# i2c_stm32.net
KiCad netlist of a schematic drawn in EAGLE
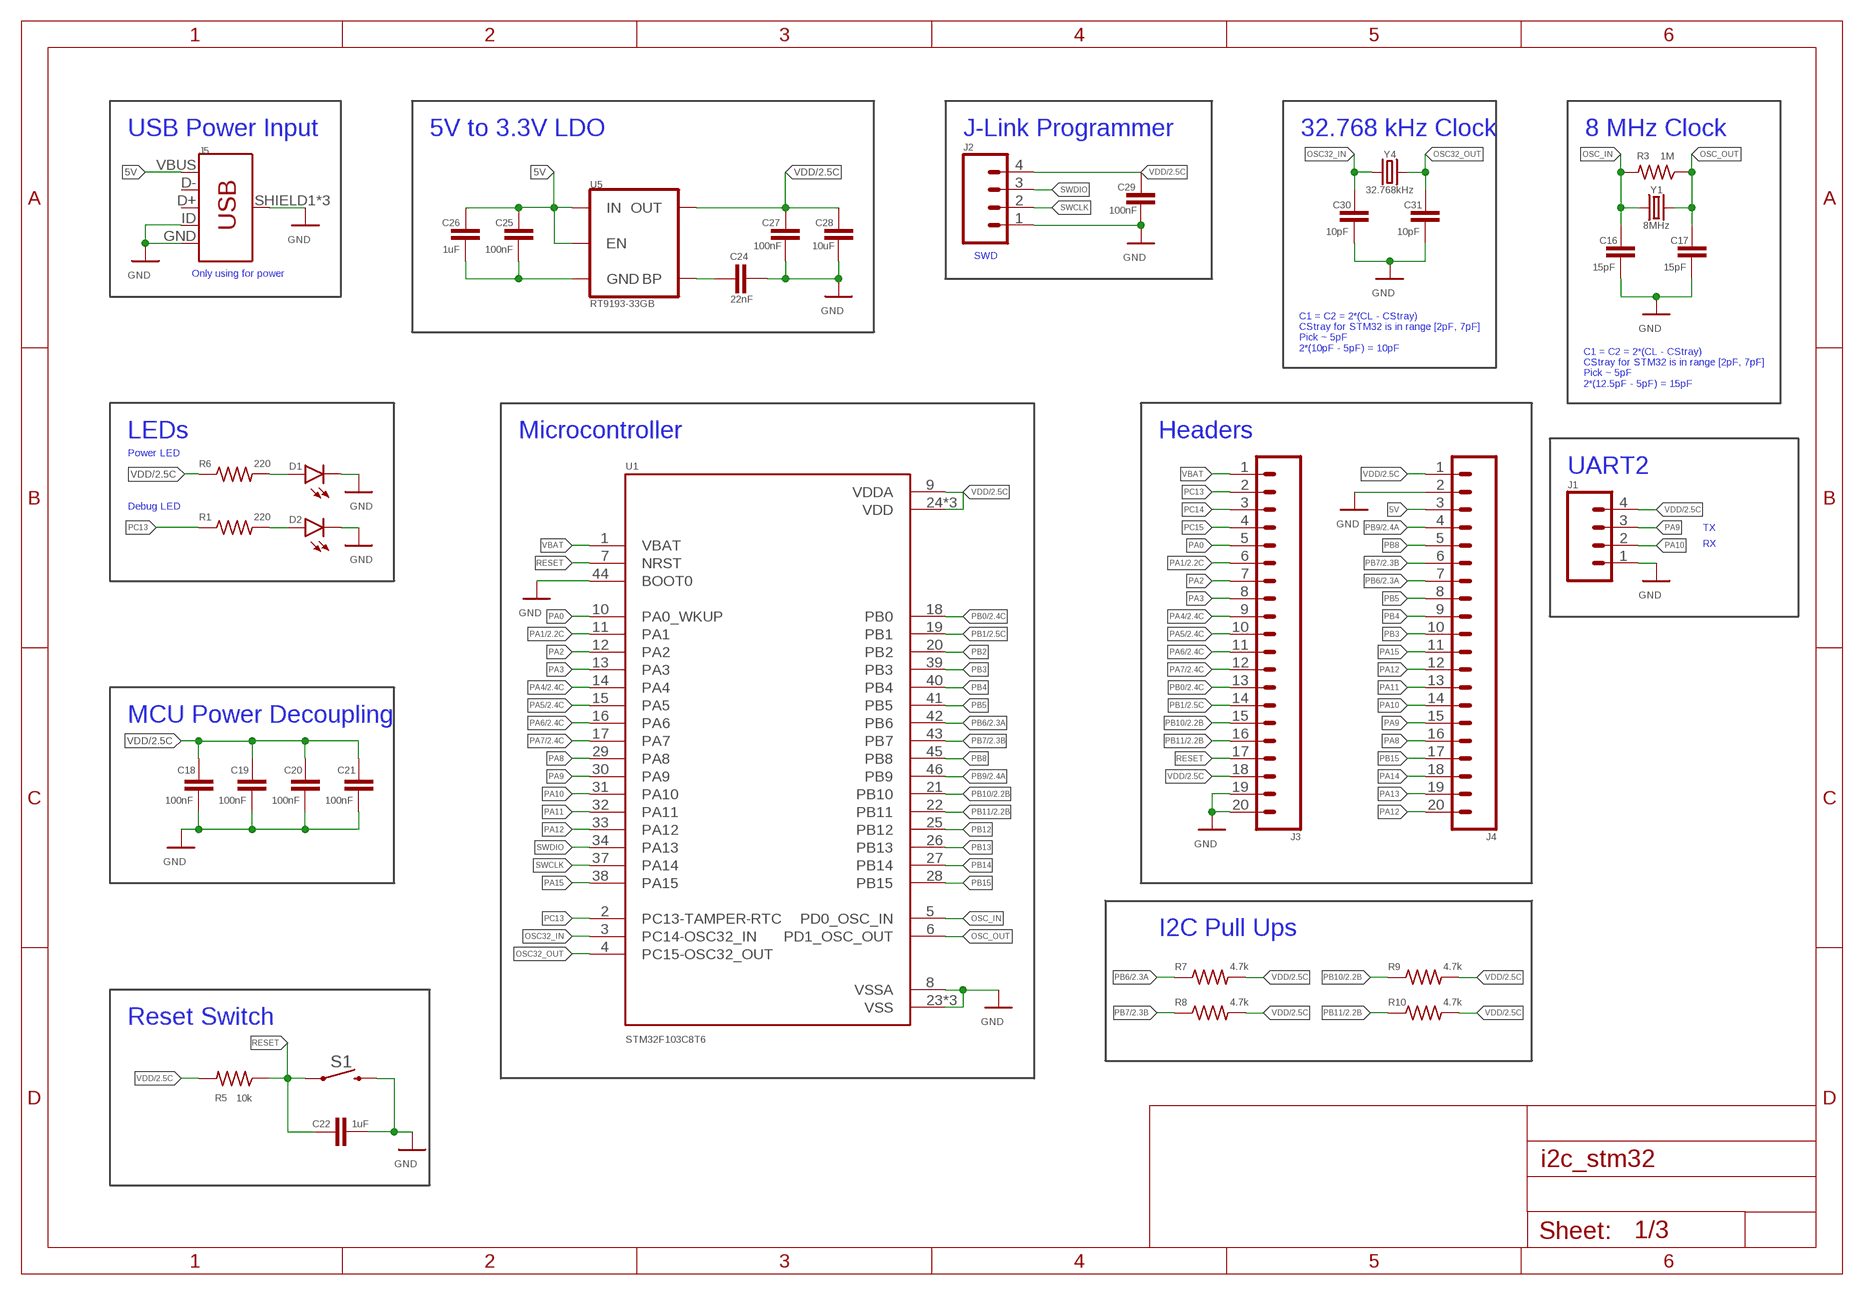
[diagram p0: schematic, sheet 1]
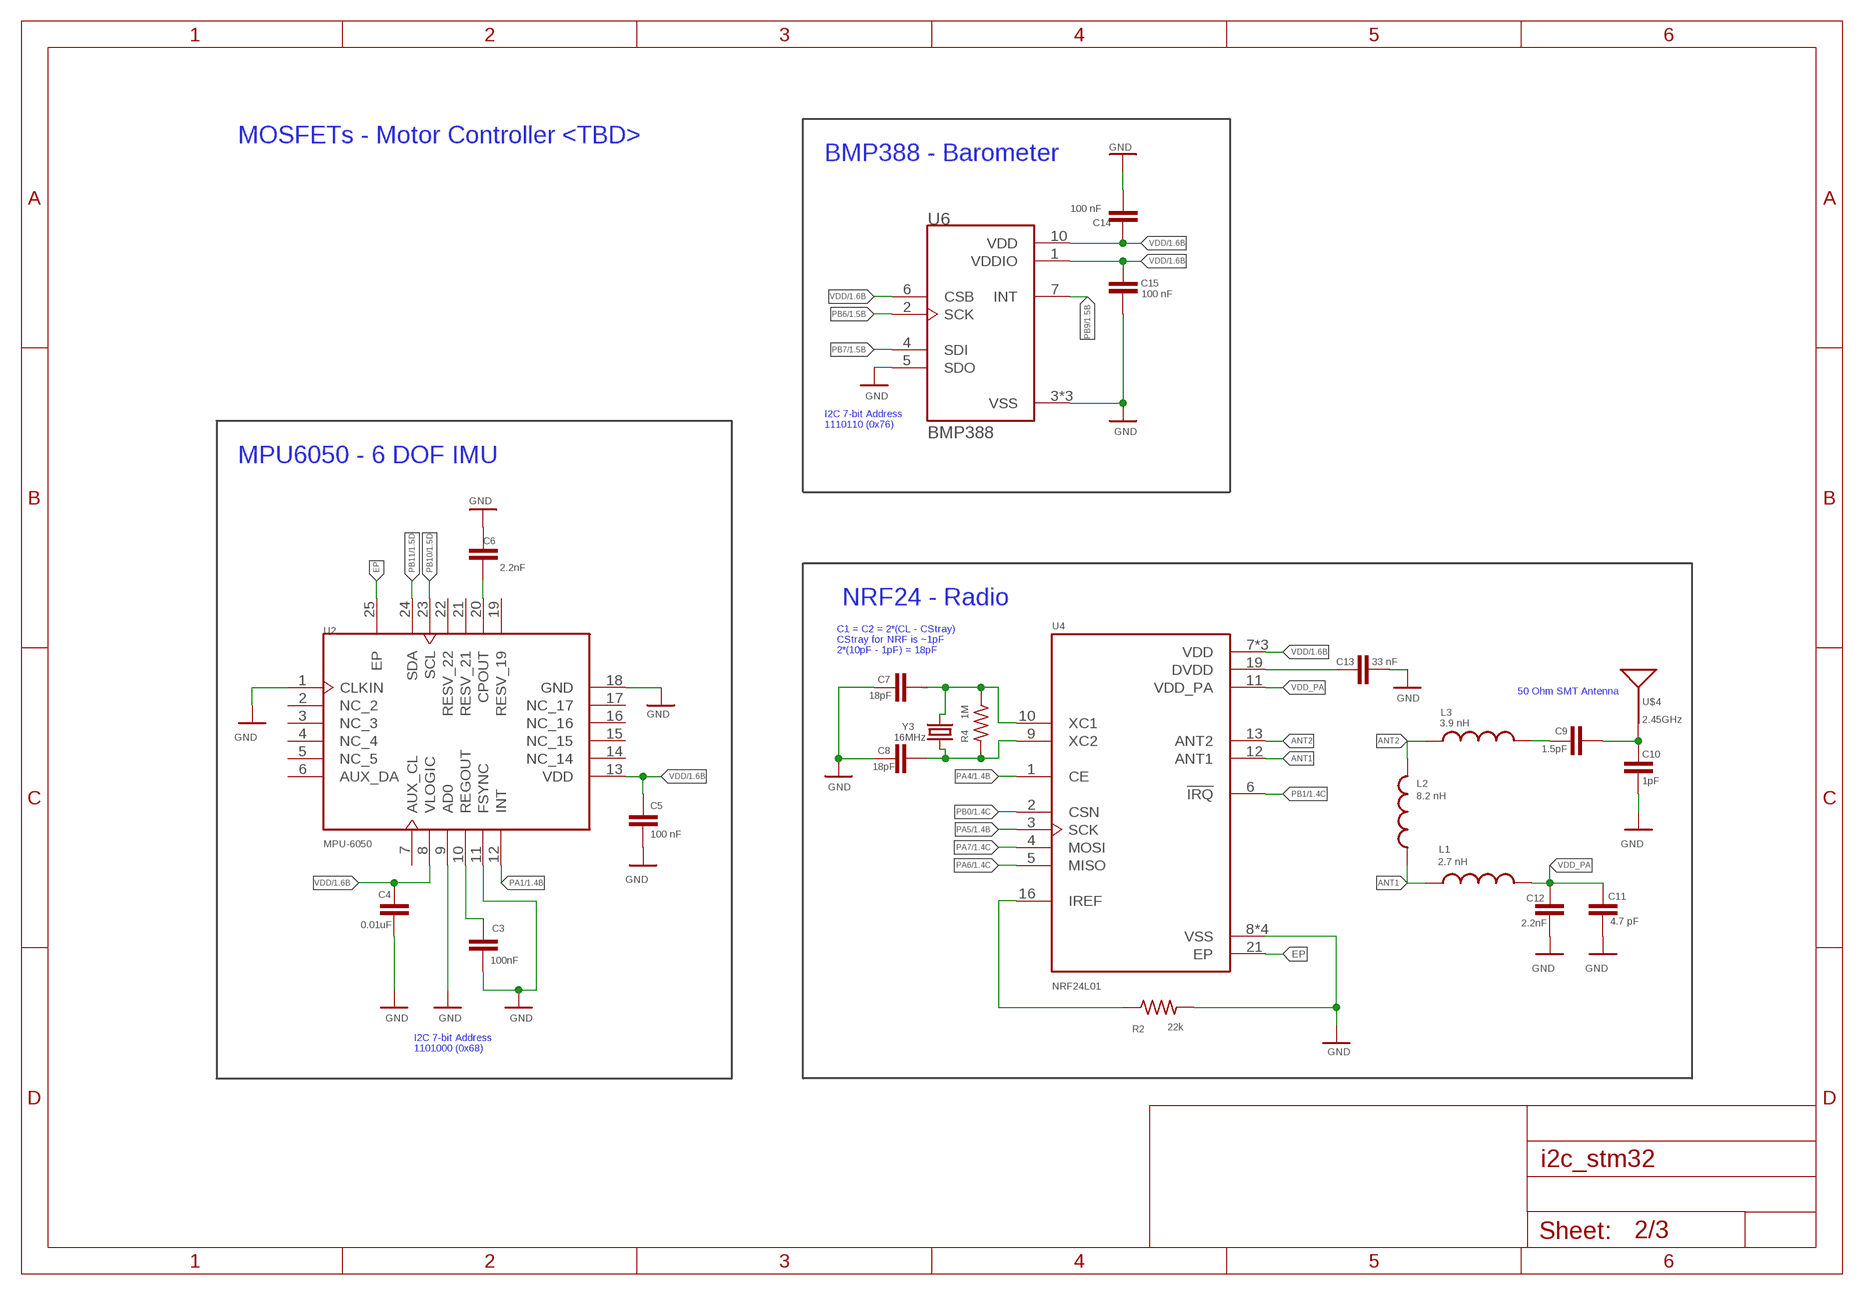
[diagram p1: schematic, sheet 2]
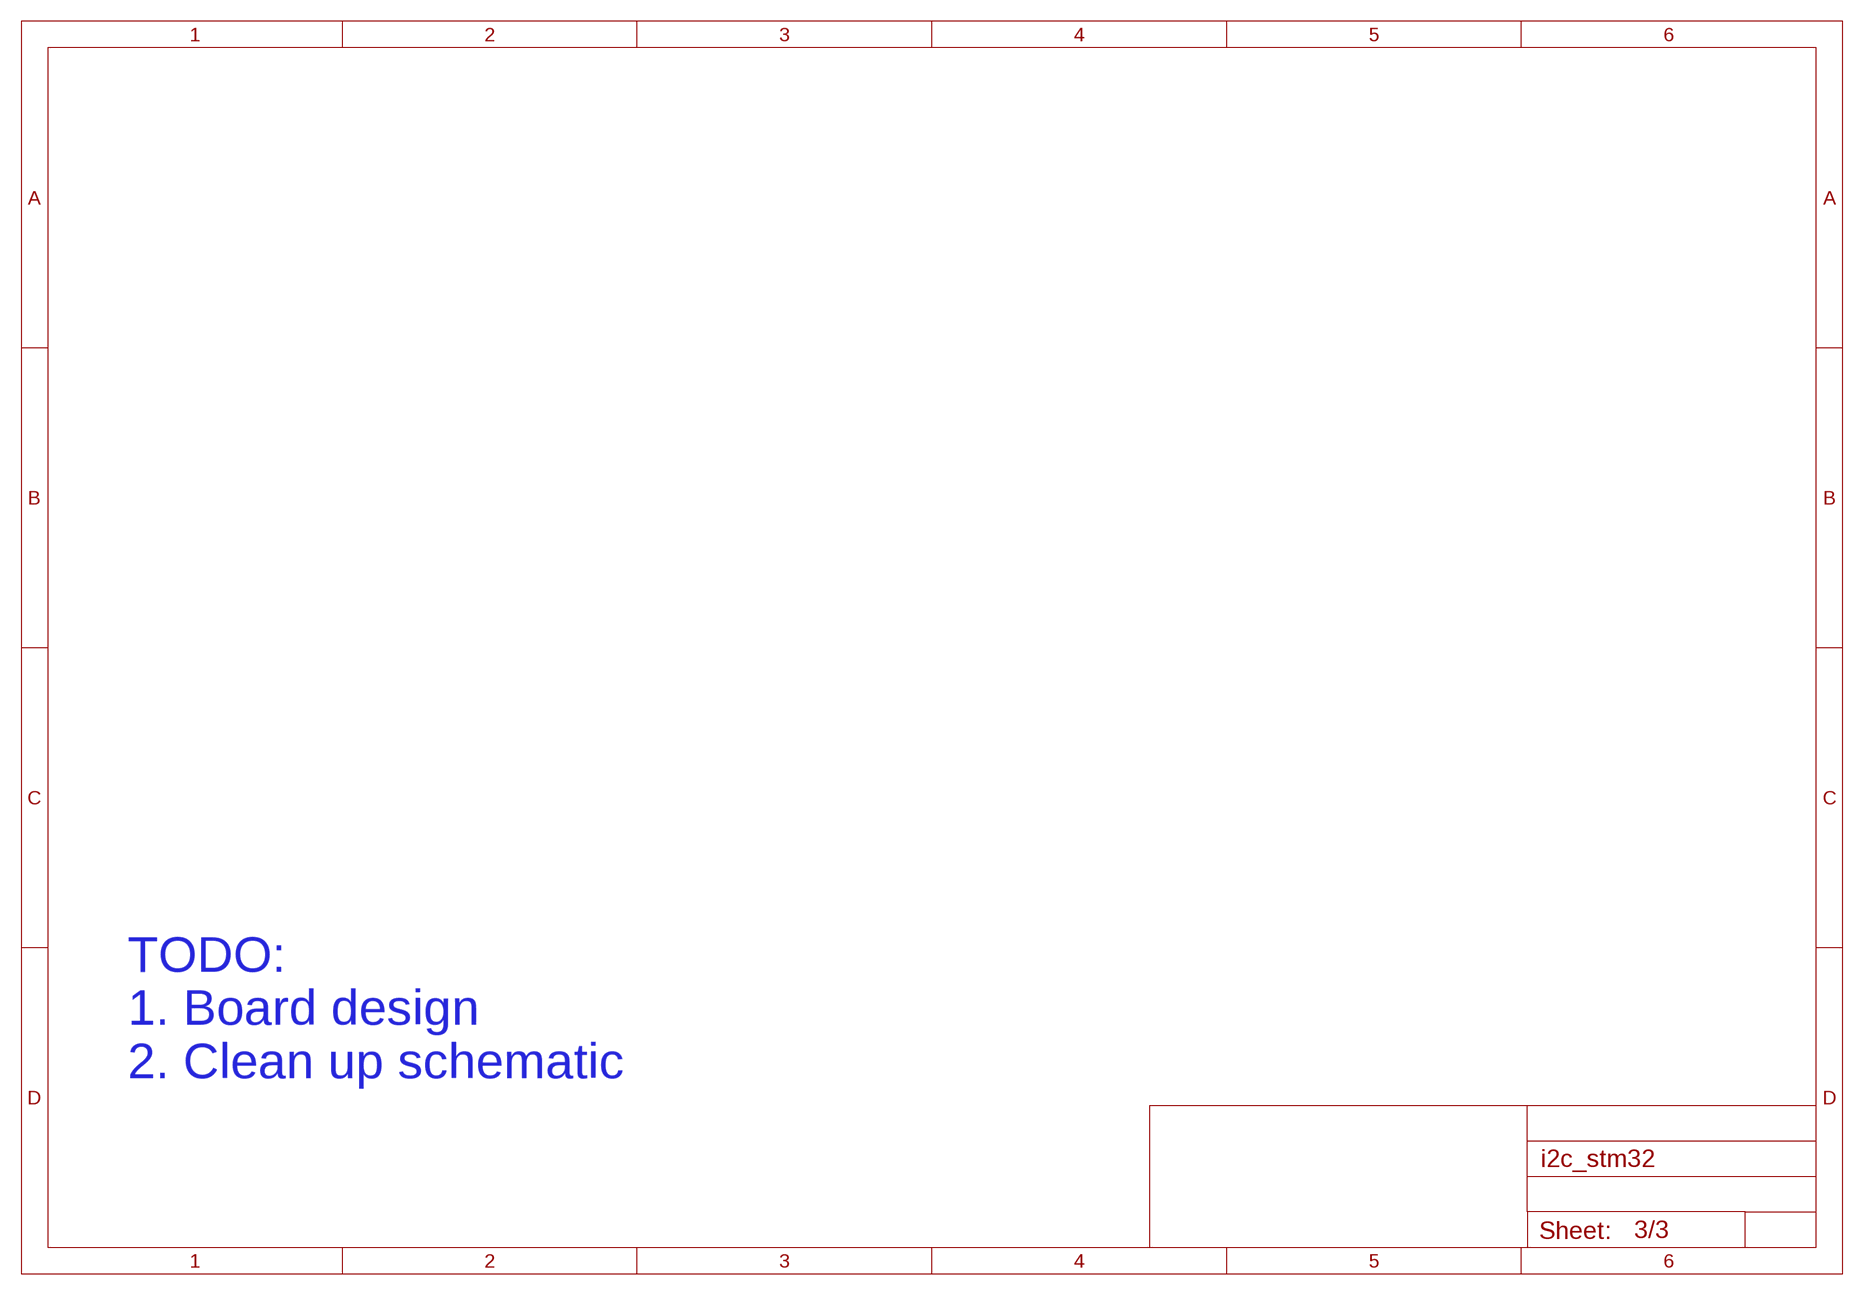
[diagram p2: schematic, sheet 3]

(export (version "E")
  (design (tool "Eeschema 10.0.6"))
  (components
    (comp (ref "C3")
      (value "100nF")
      (footprint "eagle-import:CAP_0603")
      (fields
        (field (name "DIGIKEY_PART_NUMBER") "399-7814-2-ND")
        (field (name "MANUFACTURER") "KEMET")
        (field (name "MPN") "C0603C100C5GACTU")
        (field (name "CREATED_BY") "PCBLayout.com")
      )
      (libsource (lib "eagle-import") (part "C0603C100C5GACTU"))
    )
    (comp (ref "C4")
      (value "0.01uF")
      (footprint "eagle-import:CAP_0603")
      (fields
        (field (name "DIGIKEY_PART_NUMBER") "399-7814-2-ND")
        (field (name "MANUFACTURER") "KEMET")
        (field (name "MPN") "C0603C100C5GACTU")
        (field (name "CREATED_BY") "PCBLayout.com")
      )
      (libsource (lib "eagle-import") (part "C0603C100C5GACTU"))
    )
    (comp (ref "C5")
      (value "100 nF")
      (footprint "eagle-import:CAP_0603")
      (fields
        (field (name "DIGIKEY_PART_NUMBER") "399-7814-2-ND")
        (field (name "MANUFACTURER") "KEMET")
        (field (name "MPN") "C0603C100C5GACTU")
        (field (name "CREATED_BY") "PCBLayout.com")
      )
      (libsource (lib "eagle-import") (part "C0603C100C5GACTU"))
    )
    (comp (ref "C6")
      (value "2.2nF")
      (footprint "eagle-import:CAP_0603")
      (fields
        (field (name "DIGIKEY_PART_NUMBER") "399-7814-2-ND")
        (field (name "MANUFACTURER") "KEMET")
        (field (name "MPN") "C0603C100C5GACTU")
        (field (name "CREATED_BY") "PCBLayout.com")
      )
      (libsource (lib "eagle-import") (part "C0603C100C5GACTU"))
    )
    (comp (ref "C7")
      (value "18pF")
      (footprint "eagle-import:CAP_0603")
      (fields
        (field (name "DIGIKEY_PART_NUMBER") "399-7814-2-ND")
        (field (name "MANUFACTURER") "KEMET")
        (field (name "MPN") "C0603C100C5GACTU")
        (field (name "CREATED_BY") "PCBLayout.com")
      )
      (libsource (lib "eagle-import") (part "C0603C100C5GACTU"))
    )
    (comp (ref "C8")
      (value "18pF")
      (footprint "eagle-import:CAP_0603")
      (fields
        (field (name "DIGIKEY_PART_NUMBER") "399-7814-2-ND")
        (field (name "MANUFACTURER") "KEMET")
        (field (name "MPN") "C0603C100C5GACTU")
        (field (name "CREATED_BY") "PCBLayout.com")
      )
      (libsource (lib "eagle-import") (part "C0603C100C5GACTU"))
    )
    (comp (ref "C9")
      (value "1.5pF")
      (footprint "eagle-import:CAP_0603")
      (fields
        (field (name "DIGIKEY_PART_NUMBER") "399-7814-2-ND")
        (field (name "MANUFACTURER") "KEMET")
        (field (name "MPN") "C0603C100C5GACTU")
        (field (name "CREATED_BY") "PCBLayout.com")
      )
      (libsource (lib "eagle-import") (part "C0603C100C5GACTU"))
    )
    (comp (ref "C10")
      (value "1pF")
      (footprint "eagle-import:CAP_0603")
      (fields
        (field (name "DIGIKEY_PART_NUMBER") "399-7814-2-ND")
        (field (name "MANUFACTURER") "KEMET")
        (field (name "MPN") "C0603C100C5GACTU")
        (field (name "CREATED_BY") "PCBLayout.com")
      )
      (libsource (lib "eagle-import") (part "C0603C100C5GACTU"))
    )
    (comp (ref "C11")
      (value "4.7 pF")
      (footprint "eagle-import:CAP_0603")
      (fields
        (field (name "DIGIKEY_PART_NUMBER") "399-7814-2-ND")
        (field (name "MANUFACTURER") "KEMET")
        (field (name "MPN") "C0603C100C5GACTU")
        (field (name "CREATED_BY") "PCBLayout.com")
      )
      (libsource (lib "eagle-import") (part "C0603C100C5GACTU"))
    )
    (comp (ref "C12")
      (value "2.2nF")
      (footprint "eagle-import:CAP_0603")
      (fields
        (field (name "DIGIKEY_PART_NUMBER") "399-7814-2-ND")
        (field (name "MANUFACTURER") "KEMET")
        (field (name "MPN") "C0603C100C5GACTU")
        (field (name "CREATED_BY") "PCBLayout.com")
      )
      (libsource (lib "eagle-import") (part "C0603C100C5GACTU"))
    )
    (comp (ref "C13")
      (value "33 nF")
      (footprint "eagle-import:CAP_0603")
      (fields
        (field (name "DIGIKEY_PART_NUMBER") "399-7814-2-ND")
        (field (name "MANUFACTURER") "KEMET")
        (field (name "MPN") "C0603C100C5GACTU")
        (field (name "CREATED_BY") "PCBLayout.com")
      )
      (libsource (lib "eagle-import") (part "C0603C100C5GACTU"))
    )
    (comp (ref "C14")
      (value "100 nF")
      (footprint "eagle-import:CAP_0603")
      (fields
        (field (name "DIGIKEY_PART_NUMBER") "399-7814-2-ND")
        (field (name "MANUFACTURER") "KEMET")
        (field (name "MPN") "C0603C100C5GACTU")
        (field (name "CREATED_BY") "PCBLayout.com")
      )
      (libsource (lib "eagle-import") (part "C0603C100C5GACTU"))
    )
    (comp (ref "C15")
      (value "100 nF")
      (footprint "eagle-import:CAP_0603")
      (fields
        (field (name "DIGIKEY_PART_NUMBER") "399-7814-2-ND")
        (field (name "MANUFACTURER") "KEMET")
        (field (name "MPN") "C0603C100C5GACTU")
        (field (name "CREATED_BY") "PCBLayout.com")
      )
      (libsource (lib "eagle-import") (part "C0603C100C5GACTU"))
    )
    (comp (ref "L1")
      (value "2.7 nH")
      (footprint "eagle-import:RESC0603_M")
      (libsource (lib "eagle-import") (part "INDUCTOR_0603_M"))
    )
    (comp (ref "L2")
      (value "8.2 nH")
      (footprint "eagle-import:RESC0603_M")
      (libsource (lib "eagle-import") (part "INDUCTOR_0603_M"))
    )
    (comp (ref "L3")
      (value "3.9 nH")
      (footprint "eagle-import:RESC0603_M")
      (libsource (lib "eagle-import") (part "INDUCTOR_0603_M"))
    )
    (comp (ref "R2")
      (value "22k")
      (footprint "eagle-import:RES_0603")
      (fields
        (field (name "DIGIKEY_PART_NUMBER") "311-0.0GRTR-ND")
        (field (name "MANUFACTURER") "Yageo")
        (field (name "MPN") "RC0603JR-070RL")
        (field (name "CREATED_BY") "PCBLayout.com")
      )
      (libsource (lib "eagle-import") (part "RC0603JR-070RL"))
    )
    (comp (ref "R4")
      (value "1M")
      (footprint "eagle-import:RES_0603")
      (fields
        (field (name "DIGIKEY_PART_NUMBER") "311-0.0GRTR-ND")
        (field (name "MANUFACTURER") "Yageo")
        (field (name "MPN") "RC0603JR-070RL")
        (field (name "CREATED_BY") "PCBLayout.com")
      )
      (libsource (lib "eagle-import") (part "RC0603JR-070RL"))
    )
    (comp (ref "U$4")
      (value "2.45GHz")
      (footprint "eagle-import:ANT-2.4GHZ-6.5X2.2MM")
      (libsource (lib "eagle-import") (part "ANTENNA2.4GHZ-6.5X2.2MM"))
    )
    (comp (ref "U2")
      (value "MPU-6050")
      (footprint "eagle-import:24-VFQFN")
      (fields
        (field (name "DIGIKEY_PART_NUMBER") "1428-1007-1-ND")
        (field (name "MANUFACTURER") "TDK InvenSense")
        (field (name "CREATED_BY") "PCBLayout.com")
      )
      (libsource (lib "eagle-import") (part "MPU-6050"))
    )
    (comp (ref "U4")
      (value "NRF24L01")
      (footprint "eagle-import:QFN50P400X400X95-21N")
      (fields (field (name "MF") "Nordic"))
      (libsource (lib "eagle-import") (part "NRF24L01"))
    )
    (comp (ref "U6")
      (value "BMP388")
      (footprint "eagle-import:PQFN50P200X200X80-10N")
      (fields (field (name "DIGI-KEY_PART_NUMBER") "828-1079-1-ND") (field (name "MF") "Bosch Sensortec"))
      (libsource (lib "eagle-import") (part "BMP388"))
    )
    (comp (ref "Y3")
      (value "16MHz")
      (footprint "eagle-import:CRYSTAL-SMD-5X3.2-4PAD")
      (libsource (lib "eagle-import") (part "CRYSTAL-16MHZSMD-5X3.2"))
    )
    (comp (ref "C16")
      (value "15pF")
      (footprint "eagle-import:CAP_0603")
      (fields
        (field (name "DIGIKEY_PART_NUMBER") "399-7814-2-ND")
        (field (name "MANUFACTURER") "KEMET")
        (field (name "MPN") "C0603C100C5GACTU")
        (field (name "CREATED_BY") "PCBLayout.com")
      )
      (libsource (lib "eagle-import") (part "C0603C100C5GACTU"))
    )
    (comp (ref "C17")
      (value "15pF")
      (footprint "eagle-import:CAP_0603")
      (fields
        (field (name "DIGIKEY_PART_NUMBER") "399-7814-2-ND")
        (field (name "MANUFACTURER") "KEMET")
        (field (name "MPN") "C0603C100C5GACTU")
        (field (name "CREATED_BY") "PCBLayout.com")
      )
      (libsource (lib "eagle-import") (part "C0603C100C5GACTU"))
    )
    (comp (ref "C18")
      (value "100nF")
      (footprint "eagle-import:CAP_0603")
      (fields
        (field (name "DIGIKEY_PART_NUMBER") "399-7814-2-ND")
        (field (name "MANUFACTURER") "KEMET")
        (field (name "MPN") "C0603C100C5GACTU")
        (field (name "CREATED_BY") "PCBLayout.com")
      )
      (libsource (lib "eagle-import") (part "C0603C100C5GACTU"))
    )
    (comp (ref "C19")
      (value "100nF")
      (footprint "eagle-import:CAP_0603")
      (fields
        (field (name "DIGIKEY_PART_NUMBER") "399-7814-2-ND")
        (field (name "MANUFACTURER") "KEMET")
        (field (name "MPN") "C0603C100C5GACTU")
        (field (name "CREATED_BY") "PCBLayout.com")
      )
      (libsource (lib "eagle-import") (part "C0603C100C5GACTU"))
    )
    (comp (ref "C20")
      (value "100nF")
      (footprint "eagle-import:CAP_0603")
      (fields
        (field (name "DIGIKEY_PART_NUMBER") "399-7814-2-ND")
        (field (name "MANUFACTURER") "KEMET")
        (field (name "MPN") "C0603C100C5GACTU")
        (field (name "CREATED_BY") "PCBLayout.com")
      )
      (libsource (lib "eagle-import") (part "C0603C100C5GACTU"))
    )
    (comp (ref "C21")
      (value "100nF")
      (footprint "eagle-import:CAP_0603")
      (fields
        (field (name "DIGIKEY_PART_NUMBER") "399-7814-2-ND")
        (field (name "MANUFACTURER") "KEMET")
        (field (name "MPN") "C0603C100C5GACTU")
        (field (name "CREATED_BY") "PCBLayout.com")
      )
      (libsource (lib "eagle-import") (part "C0603C100C5GACTU"))
    )
    (comp (ref "C22")
      (value "1uF")
      (footprint "eagle-import:CAP_0603")
      (fields
        (field (name "DIGIKEY_PART_NUMBER") "399-7814-2-ND")
        (field (name "MANUFACTURER") "KEMET")
        (field (name "MPN") "C0603C100C5GACTU")
        (field (name "CREATED_BY") "PCBLayout.com")
      )
      (libsource (lib "eagle-import") (part "C0603C100C5GACTU"))
    )
    (comp (ref "C24")
      (value "22nF")
      (footprint "eagle-import:CAP_0603")
      (fields
        (field (name "DIGIKEY_PART_NUMBER") "399-7814-2-ND")
        (field (name "MANUFACTURER") "KEMET")
        (field (name "MPN") "C0603C100C5GACTU")
        (field (name "CREATED_BY") "PCBLayout.com")
      )
      (libsource (lib "eagle-import") (part "C0603C100C5GACTU"))
    )
    (comp (ref "C25")
      (value "100nF")
      (footprint "eagle-import:CAP_0603")
      (fields
        (field (name "DIGIKEY_PART_NUMBER") "399-7814-2-ND")
        (field (name "MANUFACTURER") "KEMET")
        (field (name "MPN") "C0603C100C5GACTU")
        (field (name "CREATED_BY") "PCBLayout.com")
      )
      (libsource (lib "eagle-import") (part "C0603C100C5GACTU"))
    )
    (comp (ref "C26")
      (value "1uF")
      (footprint "eagle-import:CAP_0603")
      (fields
        (field (name "DIGIKEY_PART_NUMBER") "399-7814-2-ND")
        (field (name "MANUFACTURER") "KEMET")
        (field (name "MPN") "C0603C100C5GACTU")
        (field (name "CREATED_BY") "PCBLayout.com")
      )
      (libsource (lib "eagle-import") (part "C0603C100C5GACTU"))
    )
    (comp (ref "C27")
      (value "100nF")
      (footprint "eagle-import:CAP_0603")
      (fields
        (field (name "DIGIKEY_PART_NUMBER") "399-7814-2-ND")
        (field (name "MANUFACTURER") "KEMET")
        (field (name "MPN") "C0603C100C5GACTU")
        (field (name "CREATED_BY") "PCBLayout.com")
      )
      (libsource (lib "eagle-import") (part "C0603C100C5GACTU"))
    )
    (comp (ref "C28")
      (value "10uF")
      (footprint "eagle-import:CAP_0603")
      (fields
        (field (name "DIGIKEY_PART_NUMBER") "399-7814-2-ND")
        (field (name "MANUFACTURER") "KEMET")
        (field (name "MPN") "C0603C100C5GACTU")
        (field (name "CREATED_BY") "PCBLayout.com")
      )
      (libsource (lib "eagle-import") (part "C0603C100C5GACTU"))
    )
    (comp (ref "C29")
      (value "100nF")
      (footprint "eagle-import:CAP_0603")
      (fields
        (field (name "DIGIKEY_PART_NUMBER") "399-7814-2-ND")
        (field (name "MANUFACTURER") "KEMET")
        (field (name "MPN") "C0603C100C5GACTU")
        (field (name "CREATED_BY") "PCBLayout.com")
      )
      (libsource (lib "eagle-import") (part "C0603C100C5GACTU"))
    )
    (comp (ref "C30")
      (value "10pF")
      (footprint "eagle-import:CAP_0603")
      (fields
        (field (name "DIGIKEY_PART_NUMBER") "399-7814-2-ND")
        (field (name "MANUFACTURER") "KEMET")
        (field (name "MPN") "C0603C100C5GACTU")
        (field (name "CREATED_BY") "PCBLayout.com")
      )
      (libsource (lib "eagle-import") (part "C0603C100C5GACTU"))
    )
    (comp (ref "C31")
      (value "10pF")
      (footprint "eagle-import:CAP_0603")
      (fields
        (field (name "DIGIKEY_PART_NUMBER") "399-7814-2-ND")
        (field (name "MANUFACTURER") "KEMET")
        (field (name "MPN") "C0603C100C5GACTU")
        (field (name "CREATED_BY") "PCBLayout.com")
      )
      (libsource (lib "eagle-import") (part "C0603C100C5GACTU"))
    )
    (comp (ref "D1")
      (value "LED0603")
      (footprint "eagle-import:LED-0603")
      (libsource (lib "eagle-import") (part "LED0603"))
    )
    (comp (ref "D2")
      (value "LED0603")
      (footprint "eagle-import:LED-0603")
      (libsource (lib "eagle-import") (part "LED0603"))
    )
    (comp (ref "J1")
      (value "CONN_04")
      (footprint "eagle-import:1X04")
      (libsource (lib "eagle-import") (part "CONN_04"))
    )
    (comp (ref "J2")
      (value "CONN_04")
      (footprint "eagle-import:1X04")
      (libsource (lib "eagle-import") (part "CONN_04"))
    )
    (comp (ref "J3")
      (value "CONN_20")
      (footprint "eagle-import:1X20")
      (libsource (lib "eagle-import") (part "CONN_20"))
    )
    (comp (ref "J4")
      (value "CONN_20")
      (footprint "eagle-import:1X20")
      (libsource (lib "eagle-import") (part "CONN_20"))
    )
    (comp (ref "J5")
      (value "USB_MICRO-B_FEMALE-SMT")
      (footprint "eagle-import:USB-B-MICRO-SMD")
      (libsource (lib "eagle-import") (part "USB_MICRO-B_FEMALE-SMT"))
    )
    (comp (ref "R1")
      (value "220")
      (footprint "eagle-import:RES_0603")
      (fields
        (field (name "DIGIKEY_PART_NUMBER") "311-0.0GRTR-ND")
        (field (name "MANUFACTURER") "Yageo")
        (field (name "MPN") "RC0603JR-070RL")
        (field (name "CREATED_BY") "PCBLayout.com")
      )
      (libsource (lib "eagle-import") (part "RC0603JR-070RL"))
    )
    (comp (ref "R3")
      (value "1M")
      (footprint "eagle-import:RES_0603")
      (fields
        (field (name "DIGIKEY_PART_NUMBER") "311-0.0GRTR-ND")
        (field (name "MANUFACTURER") "Yageo")
        (field (name "MPN") "RC0603JR-070RL")
        (field (name "CREATED_BY") "PCBLayout.com")
      )
      (libsource (lib "eagle-import") (part "RC0603JR-070RL"))
    )
    (comp (ref "R5")
      (value "10k")
      (footprint "eagle-import:RES_0603")
      (fields
        (field (name "DIGIKEY_PART_NUMBER") "311-0.0GRTR-ND")
        (field (name "MANUFACTURER") "Yageo")
        (field (name "MPN") "RC0603JR-070RL")
        (field (name "CREATED_BY") "PCBLayout.com")
      )
      (libsource (lib "eagle-import") (part "RC0603JR-070RL"))
    )
    (comp (ref "R6")
      (value "220")
      (footprint "eagle-import:RES_0603")
      (fields
        (field (name "DIGIKEY_PART_NUMBER") "311-0.0GRTR-ND")
        (field (name "MANUFACTURER") "Yageo")
        (field (name "MPN") "RC0603JR-070RL")
        (field (name "CREATED_BY") "PCBLayout.com")
      )
      (libsource (lib "eagle-import") (part "RC0603JR-070RL"))
    )
    (comp (ref "R7")
      (value "4.7k")
      (footprint "eagle-import:RES_0603")
      (fields
        (field (name "DIGIKEY_PART_NUMBER") "311-0.0GRTR-ND")
        (field (name "MANUFACTURER") "Yageo")
        (field (name "MPN") "RC0603JR-070RL")
        (field (name "CREATED_BY") "PCBLayout.com")
      )
      (libsource (lib "eagle-import") (part "RC0603JR-070RL"))
    )
    (comp (ref "R8")
      (value "4.7k")
      (footprint "eagle-import:RES_0603")
      (fields
        (field (name "DIGIKEY_PART_NUMBER") "311-0.0GRTR-ND")
        (field (name "MANUFACTURER") "Yageo")
        (field (name "MPN") "RC0603JR-070RL")
        (field (name "CREATED_BY") "PCBLayout.com")
      )
      (libsource (lib "eagle-import") (part "RC0603JR-070RL"))
    )
    (comp (ref "R9")
      (value "4.7k")
      (footprint "eagle-import:RES_0603")
      (fields
        (field (name "DIGIKEY_PART_NUMBER") "311-0.0GRTR-ND")
        (field (name "MANUFACTURER") "Yageo")
        (field (name "MPN") "RC0603JR-070RL")
        (field (name "CREATED_BY") "PCBLayout.com")
      )
      (libsource (lib "eagle-import") (part "RC0603JR-070RL"))
    )
    (comp (ref "R10")
      (value "4.7k")
      (footprint "eagle-import:RES_0603")
      (fields
        (field (name "DIGIKEY_PART_NUMBER") "311-0.0GRTR-ND")
        (field (name "MANUFACTURER") "Yageo")
        (field (name "MPN") "RC0603JR-070RL")
        (field (name "CREATED_BY") "PCBLayout.com")
      )
      (libsource (lib "eagle-import") (part "RC0603JR-070RL"))
    )
    (comp (ref "S1")
      (value "MOMENTARY-SWITCH-SPST-PTH-6.0MM")
      (footprint "eagle-import:TACTILE_SWITCH_PTH_6.0MM")
      (libsource (lib "eagle-import") (part "MOMENTARY-SWITCH-SPST-PTH-6.0MM"))
    )
    (comp (ref "U1")
      (value "STM32F103C8T6")
      (footprint "eagle-import:QFP50P900X900X160-48N")
      (fields (field (name "MF") "STMicroelectronics") (field (name "SPICEPREFIX") "X"))
      (libsource (lib "eagle-import") (part "STM32F103C8T6"))
    )
    (comp (ref "U5")
      (value "RT9193-33GB")
      (footprint "eagle-import:SOT23-5")
      (libsource (lib "eagle-import") (part "V_REG_MIC5205ADJ"))
    )
    (comp (ref "Y1")
      (value "8MHz")
      (footprint "eagle-import:CRYSTAL-SMD-5X3.2-4PAD")
      (libsource (lib "eagle-import") (part "CRYSTAL-8MHZSMD-5X3.2"))
    )
    (comp (ref "Y4")
      (value "32.768kHz")
      (footprint "eagle-import:CRYSTAL-SMD-3.2X1.5MM")
      (libsource (lib "eagle-import") (part "CRYSTAL-32.768KHZSMD-3.2X1.5"))
    )
  )
  (nets
    (net (code "1") (name "5V") (class "Default")
      (node (ref "C25") (pin "2") (pinfunction "2_2") (pintype "passive"))
      (node (ref "C26") (pin "2") (pinfunction "2_2") (pintype "passive"))
      (node (ref "J4") (pin "3") (pinfunction "3_3") (pintype "passive"))
      (node (ref "J5") (pin "VBUS") (pinfunction "VBUS_VBUS") (pintype "power_in"))
      (node (ref "U5") (pin "1") (pinfunction "IN_1") (pintype "input"))
      (node (ref "U5") (pin "3") (pinfunction "EN_3") (pintype "input"))
    )
    (net (code "2") (name "ANT1") (class "Default")
      (node (ref "L1") (pin "1") (pinfunction "1_1") (pintype "passive"))
      (node (ref "L2") (pin "1") (pinfunction "1_1") (pintype "passive"))
      (node (ref "U4") (pin "12") (pinfunction "ANT1_12") (pintype "bidirectional"))
    )
    (net (code "3") (name "ANT2") (class "Default")
      (node (ref "L2") (pin "2") (pinfunction "2_2") (pintype "passive"))
      (node (ref "L3") (pin "1") (pinfunction "1_1") (pintype "passive"))
      (node (ref "U4") (pin "13") (pinfunction "ANT2_13") (pintype "bidirectional"))
    )
    (net (code "4") (name "EP") (class "Default")
      (node (ref "U2") (pin "25") (pinfunction "EP_25") (pintype "power_in"))
      (node (ref "U4") (pin "21") (pinfunction "EP_21") (pintype "power_in"))
    )
    (net (code "5") (name "GND") (class "Default")
      (node (ref "C10") (pin "1") (pinfunction "1_1") (pintype "passive"))
      (node (ref "C11") (pin "1") (pinfunction "1_1") (pintype "passive"))
      (node (ref "C12") (pin "1") (pinfunction "1_1") (pintype "passive"))
      (node (ref "C13") (pin "2") (pinfunction "2_2") (pintype "passive"))
      (node (ref "C14") (pin "2") (pinfunction "2_2") (pintype "passive"))
      (node (ref "C15") (pin "1") (pinfunction "1_1") (pintype "passive"))
      (node (ref "C16") (pin "2") (pinfunction "2_2") (pintype "passive"))
      (node (ref "C17") (pin "2") (pinfunction "2_2") (pintype "passive"))
      (node (ref "C18") (pin "2") (pinfunction "2_2") (pintype "passive"))
      (node (ref "C19") (pin "2") (pinfunction "2_2") (pintype "passive"))
      (node (ref "C20") (pin "2") (pinfunction "2_2") (pintype "passive"))
      (node (ref "C21") (pin "2") (pinfunction "2_2") (pintype "passive"))
      (node (ref "C22") (pin "2") (pinfunction "2_2") (pintype "passive"))
      (node (ref "C24") (pin "1") (pinfunction "1_1") (pintype "passive"))
      (node (ref "C27") (pin "2") (pinfunction "2_2") (pintype "passive"))
      (node (ref "C28") (pin "2") (pinfunction "2_2") (pintype "passive"))
      (node (ref "C29") (pin "2") (pinfunction "2_2") (pintype "passive"))
      (node (ref "C3") (pin "2") (pinfunction "2_2") (pintype "passive"))
      (node (ref "C30") (pin "2") (pinfunction "2_2") (pintype "passive"))
      (node (ref "C31") (pin "2") (pinfunction "2_2") (pintype "passive"))
      (node (ref "C4") (pin "2") (pinfunction "2_2") (pintype "passive"))
      (node (ref "C5") (pin "2") (pinfunction "2_2") (pintype "passive"))
      (node (ref "C6") (pin "2") (pinfunction "2_2") (pintype "passive"))
      (node (ref "C7") (pin "2") (pinfunction "2_2") (pintype "passive"))
      (node (ref "C8") (pin "2") (pinfunction "2_2") (pintype "passive"))
      (node (ref "D1") (pin "C") (pinfunction "C_C") (pintype "passive"))
      (node (ref "D2") (pin "C") (pinfunction "C_C") (pintype "passive"))
      (node (ref "J1") (pin "1") (pinfunction "1_1") (pintype "passive"))
      (node (ref "J2") (pin "1") (pinfunction "1_1") (pintype "passive"))
      (node (ref "J3") (pin "19") (pinfunction "19_19") (pintype "passive"))
      (node (ref "J3") (pin "20") (pinfunction "20_20") (pintype "passive"))
      (node (ref "J4") (pin "2") (pinfunction "2_2") (pintype "passive"))
      (node (ref "J5") (pin "GND") (pinfunction "GND_GND") (pintype "power_in"))
      (node (ref "J5") (pin "ID") (pinfunction "ID_ID") (pintype "bidirectional"))
      (node (ref "J5") (pin "SHIELD1") (pinfunction "SHIELD_SHIELD1") (pintype "bidirectional"))
      (node (ref "J5") (pin "SHIELD2") (pinfunction "SHIELD_SHIELD2") (pintype "bidirectional"))
      (node (ref "J5") (pin "SHIELD3") (pinfunction "SHIELD_SHIELD3") (pintype "bidirectional"))
      (node (ref "R2") (pin "2") (pinfunction "2_2") (pintype "passive"))
      (node (ref "S1") (pin "3") (pinfunction "2_3") (pintype "passive"))
      (node (ref "U1") (pin "23") (pinfunction "VSS_23") (pintype "power_in"))
      (node (ref "U1") (pin "35") (pinfunction "VSS_35") (pintype "power_in"))
      (node (ref "U1") (pin "44") (pinfunction "BOOT0_44") (pintype "input"))
      (node (ref "U1") (pin "47") (pinfunction "VSS_47") (pintype "power_in"))
      (node (ref "U1") (pin "8") (pinfunction "VSSA_8") (pintype "power_in"))
      (node (ref "U2") (pin "1") (pinfunction "CLKIN_1") (pintype "input"))
      (node (ref "U2") (pin "11") (pinfunction "FSYNC_11") (pintype "input"))
      (node (ref "U2") (pin "18") (pinfunction "GND_18") (pintype "power_in"))
      (node (ref "U2") (pin "9") (pinfunction "AD0_9") (pintype "bidirectional"))
      (node (ref "U4") (pin "14") (pinfunction "VSS_14") (pintype "power_in"))
      (node (ref "U4") (pin "17") (pinfunction "VSS_17") (pintype "power_in"))
      (node (ref "U4") (pin "20") (pinfunction "VSS_20") (pintype "power_in"))
      (node (ref "U4") (pin "8") (pinfunction "VSS_8") (pintype "power_in"))
      (node (ref "U6") (pin "3") (pinfunction "VSS_3") (pintype "power_in"))
      (node (ref "U6") (pin "5") (pinfunction "SDO_5") (pintype "bidirectional"))
      (node (ref "U6") (pin "8") (pinfunction "VSS_8") (pintype "power_in"))
      (node (ref "U6") (pin "9") (pinfunction "VSS_9") (pintype "power_in"))
    )
    (net (code "6") (name "Net-(C9-Pad1)") (class "Default")
      (node (ref "C9") (pin "1") (pinfunction "1_1") (pintype "passive"))
      (node (ref "L3") (pin "2") (pinfunction "2_2") (pintype "passive"))
    )
    (net (code "7") (name "Net-(D1-PadA)") (class "Default")
      (node (ref "D1") (pin "A") (pinfunction "A_A") (pintype "passive"))
      (node (ref "R6") (pin "2") (pinfunction "2_2") (pintype "passive"))
    )
    (net (code "8") (name "Net-(D2-PadA)") (class "Default")
      (node (ref "D2") (pin "A") (pinfunction "A_A") (pintype "passive"))
      (node (ref "R1") (pin "2") (pinfunction "2_2") (pintype "passive"))
    )
    (net (code "9") (name "Net-(U$4-SIGNAL)") (class "Default")
      (node (ref "C10") (pin "2") (pinfunction "2_2") (pintype "passive"))
      (node (ref "C9") (pin "2") (pinfunction "2_2") (pintype "passive"))
      (node (ref "U$4") (pin "FEED") (pinfunction "SIGNAL_FEED") (pintype "bidirectional"))
    )
    (net (code "10") (name "Net-(U2-CPOUT)") (class "Default")
      (node (ref "C6") (pin "1") (pinfunction "1_1") (pintype "passive"))
      (node (ref "U2") (pin "20") (pinfunction "CPOUT_20") (pintype "output"))
    )
    (net (code "11") (name "Net-(U2-REGOUT)") (class "Default")
      (node (ref "C3") (pin "1") (pinfunction "1_1") (pintype "passive"))
      (node (ref "U2") (pin "10") (pinfunction "REGOUT_10") (pintype "passive"))
    )
    (net (code "12") (name "Net-(U4-DVDD)") (class "Default")
      (node (ref "C13") (pin "1") (pinfunction "1_1") (pintype "passive"))
      (node (ref "U4") (pin "19") (pinfunction "DVDD_19") (pintype "power_in"))
    )
    (net (code "13") (name "Net-(U4-IREF)") (class "Default")
      (node (ref "R2") (pin "1") (pinfunction "1_1") (pintype "passive"))
      (node (ref "U4") (pin "16") (pinfunction "IREF_16") (pintype "input"))
    )
    (net (code "14") (name "Net-(U4-XC1)") (class "Default")
      (node (ref "C7") (pin "1") (pinfunction "1_1") (pintype "passive"))
      (node (ref "R4") (pin "1") (pinfunction "1_1") (pintype "passive"))
      (node (ref "U4") (pin "10") (pinfunction "XC1_10") (pintype "input"))
      (node (ref "Y3") (pin "3") (pinfunction "2_3") (pintype "passive"))
    )
    (net (code "15") (name "Net-(U4-XC2)") (class "Default")
      (node (ref "C8") (pin "1") (pinfunction "1_1") (pintype "passive"))
      (node (ref "R4") (pin "2") (pinfunction "2_2") (pintype "passive"))
      (node (ref "U4") (pin "9") (pinfunction "XC2_9") (pintype "output"))
      (node (ref "Y3") (pin "1") (pinfunction "1_1") (pintype "passive"))
    )
    (net (code "16") (name "Net-(U5-BP)") (class "Default")
      (node (ref "C24") (pin "2") (pinfunction "2_2") (pintype "passive"))
      (node (ref "U5") (pin "4") (pinfunction "BP_4") (pintype "input"))
    )
    (net (code "17") (name "Net-(U5-GND)") (class "Default")
      (node (ref "C25") (pin "1") (pinfunction "1_1") (pintype "passive"))
      (node (ref "C26") (pin "1") (pinfunction "1_1") (pintype "passive"))
      (node (ref "U5") (pin "2") (pinfunction "GND_2") (pintype "input"))
    )
    (net (code "18") (name "OSC32_IN") (class "Default")
      (node (ref "C30") (pin "1") (pinfunction "1_1") (pintype "passive"))
      (node (ref "U1") (pin "3") (pinfunction "PC14-OSC32_IN_3") (pintype "bidirectional"))
      (node (ref "Y4") (pin "P$1") (pinfunction "1_P$1") (pintype "passive"))
    )
    (net (code "19") (name "OSC32_OUT") (class "Default")
      (node (ref "C31") (pin "1") (pinfunction "1_1") (pintype "passive"))
      (node (ref "U1") (pin "4") (pinfunction "PC15-OSC32_OUT_4") (pintype "bidirectional"))
      (node (ref "Y4") (pin "P$2") (pinfunction "2_P$2") (pintype "passive"))
    )
    (net (code "20") (name "OSC_IN") (class "Default")
      (node (ref "C16") (pin "1") (pinfunction "1_1") (pintype "passive"))
      (node (ref "R3") (pin "2") (pinfunction "2_2") (pintype "passive"))
      (node (ref "U1") (pin "5") (pinfunction "PD0_OSC_IN_5") (pintype "bidirectional"))
      (node (ref "Y1") (pin "1") (pinfunction "1_1") (pintype "passive"))
    )
    (net (code "21") (name "OSC_OUT") (class "Default")
      (node (ref "C17") (pin "1") (pinfunction "1_1") (pintype "passive"))
      (node (ref "R3") (pin "1") (pinfunction "1_1") (pintype "passive"))
      (node (ref "U1") (pin "6") (pinfunction "PD1_OSC_OUT_6") (pintype "bidirectional"))
      (node (ref "Y1") (pin "3") (pinfunction "2_3") (pintype "passive"))
    )
    (net (code "22") (name "PA0") (class "Default")
      (node (ref "J3") (pin "5") (pinfunction "5_5") (pintype "passive"))
      (node (ref "U1") (pin "10") (pinfunction "PA0_WKUP_10") (pintype "bidirectional"))
    )
    (net (code "23") (name "PA1") (class "Default")
      (node (ref "J3") (pin "6") (pinfunction "6_6") (pintype "passive"))
      (node (ref "U1") (pin "11") (pinfunction "PA1_11") (pintype "bidirectional"))
      (node (ref "U2") (pin "12") (pinfunction "INT_12") (pintype "output"))
    )
    (net (code "24") (name "PA2") (class "Default")
      (node (ref "J3") (pin "7") (pinfunction "7_7") (pintype "passive"))
      (node (ref "U1") (pin "12") (pinfunction "PA2_12") (pintype "bidirectional"))
    )
    (net (code "25") (name "PA3") (class "Default")
      (node (ref "J3") (pin "8") (pinfunction "8_8") (pintype "passive"))
      (node (ref "U1") (pin "13") (pinfunction "PA3_13") (pintype "bidirectional"))
    )
    (net (code "26") (name "PA4") (class "Default")
      (node (ref "J3") (pin "9") (pinfunction "9_9") (pintype "passive"))
      (node (ref "U1") (pin "14") (pinfunction "PA4_14") (pintype "bidirectional"))
      (node (ref "U4") (pin "1") (pinfunction "CE_1") (pintype "input"))
    )
    (net (code "27") (name "PA5") (class "Default")
      (node (ref "J3") (pin "10") (pinfunction "10_10") (pintype "passive"))
      (node (ref "U1") (pin "15") (pinfunction "PA5_15") (pintype "bidirectional"))
      (node (ref "U4") (pin "3") (pinfunction "SCK_3") (pintype "input"))
    )
    (net (code "28") (name "PA6") (class "Default")
      (node (ref "J3") (pin "11") (pinfunction "11_11") (pintype "passive"))
      (node (ref "U1") (pin "16") (pinfunction "PA6_16") (pintype "bidirectional"))
      (node (ref "U4") (pin "5") (pinfunction "MISO_5") (pintype "output"))
    )
    (net (code "29") (name "PA7") (class "Default")
      (node (ref "J3") (pin "12") (pinfunction "12_12") (pintype "passive"))
      (node (ref "U1") (pin "17") (pinfunction "PA7_17") (pintype "bidirectional"))
      (node (ref "U4") (pin "4") (pinfunction "MOSI_4") (pintype "input"))
    )
    (net (code "30") (name "PA8") (class "Default")
      (node (ref "J4") (pin "16") (pinfunction "16_16") (pintype "passive"))
      (node (ref "U1") (pin "29") (pinfunction "PA8_29") (pintype "bidirectional"))
    )
    (net (code "31") (name "PA9") (class "Default")
      (node (ref "J1") (pin "3") (pinfunction "3_3") (pintype "passive"))
      (node (ref "J4") (pin "15") (pinfunction "15_15") (pintype "passive"))
      (node (ref "U1") (pin "30") (pinfunction "PA9_30") (pintype "bidirectional"))
    )
    (net (code "32") (name "PA10") (class "Default")
      (node (ref "J1") (pin "2") (pinfunction "2_2") (pintype "passive"))
      (node (ref "J4") (pin "14") (pinfunction "14_14") (pintype "passive"))
      (node (ref "U1") (pin "31") (pinfunction "PA10_31") (pintype "bidirectional"))
    )
    (net (code "33") (name "PA11") (class "Default")
      (node (ref "J4") (pin "13") (pinfunction "13_13") (pintype "passive"))
      (node (ref "U1") (pin "32") (pinfunction "PA11_32") (pintype "bidirectional"))
    )
    (net (code "34") (name "PA12") (class "Default")
      (node (ref "J4") (pin "12") (pinfunction "12_12") (pintype "passive"))
      (node (ref "J4") (pin "20") (pinfunction "20_20") (pintype "passive"))
      (node (ref "U1") (pin "33") (pinfunction "PA12_33") (pintype "bidirectional"))
    )
    (net (code "35") (name "PA13") (class "Default")
      (node (ref "J4") (pin "19") (pinfunction "19_19") (pintype "passive"))
    )
    (net (code "36") (name "PA14") (class "Default")
      (node (ref "J4") (pin "18") (pinfunction "18_18") (pintype "passive"))
    )
    (net (code "37") (name "PA15") (class "Default")
      (node (ref "J4") (pin "11") (pinfunction "11_11") (pintype "passive"))
      (node (ref "U1") (pin "38") (pinfunction "PA15_38") (pintype "bidirectional"))
    )
    (net (code "38") (name "PB0") (class "Default")
      (node (ref "J3") (pin "13") (pinfunction "13_13") (pintype "passive"))
      (node (ref "U1") (pin "18") (pinfunction "PB0_18") (pintype "bidirectional"))
      (node (ref "U4") (pin "2") (pinfunction "CSN_2") (pintype "input"))
    )
    (net (code "39") (name "PB1") (class "Default")
      (node (ref "J3") (pin "14") (pinfunction "14_14") (pintype "passive"))
      (node (ref "U1") (pin "19") (pinfunction "PB1_19") (pintype "bidirectional"))
      (node (ref "U4") (pin "6") (pinfunction "~{IRQ}_6") (pintype "output"))
    )
    (net (code "40") (name "PB2") (class "Default")
      (node (ref "U1") (pin "20") (pinfunction "PB2_20") (pintype "bidirectional"))
    )
    (net (code "41") (name "PB3") (class "Default")
      (node (ref "J4") (pin "10") (pinfunction "10_10") (pintype "passive"))
      (node (ref "U1") (pin "39") (pinfunction "PB3_39") (pintype "bidirectional"))
    )
    (net (code "42") (name "PB4") (class "Default")
      (node (ref "J4") (pin "9") (pinfunction "9_9") (pintype "passive"))
      (node (ref "U1") (pin "40") (pinfunction "PB4_40") (pintype "bidirectional"))
    )
    (net (code "43") (name "PB5") (class "Default")
      (node (ref "J4") (pin "8") (pinfunction "8_8") (pintype "passive"))
      (node (ref "U1") (pin "41") (pinfunction "PB5_41") (pintype "bidirectional"))
    )
    (net (code "44") (name "PB6") (class "Default")
      (node (ref "J4") (pin "7") (pinfunction "7_7") (pintype "passive"))
      (node (ref "R7") (pin "1") (pinfunction "1_1") (pintype "passive"))
      (node (ref "U1") (pin "42") (pinfunction "PB6_42") (pintype "bidirectional"))
      (node (ref "U6") (pin "2") (pinfunction "SCK_2") (pintype "input"))
    )
    (net (code "45") (name "PB7") (class "Default")
      (node (ref "J4") (pin "6") (pinfunction "6_6") (pintype "passive"))
      (node (ref "R8") (pin "1") (pinfunction "1_1") (pintype "passive"))
      (node (ref "U1") (pin "43") (pinfunction "PB7_43") (pintype "bidirectional"))
      (node (ref "U6") (pin "4") (pinfunction "SDI_4") (pintype "bidirectional"))
    )
    (net (code "46") (name "PB8") (class "Default")
      (node (ref "J4") (pin "5") (pinfunction "5_5") (pintype "passive"))
      (node (ref "U1") (pin "45") (pinfunction "PB8_45") (pintype "bidirectional"))
    )
    (net (code "47") (name "PB9") (class "Default")
      (node (ref "J4") (pin "4") (pinfunction "4_4") (pintype "passive"))
      (node (ref "U1") (pin "46") (pinfunction "PB9_46") (pintype "bidirectional"))
      (node (ref "U6") (pin "7") (pinfunction "INT_7") (pintype "output"))
    )
    (net (code "48") (name "PB10") (class "Default")
      (node (ref "J3") (pin "15") (pinfunction "15_15") (pintype "passive"))
      (node (ref "R9") (pin "1") (pinfunction "1_1") (pintype "passive"))
      (node (ref "U1") (pin "21") (pinfunction "PB10_21") (pintype "bidirectional"))
      (node (ref "U2") (pin "23") (pinfunction "SCL_23") (pintype "bidirectional"))
    )
    (net (code "49") (name "PB11") (class "Default")
      (node (ref "J3") (pin "16") (pinfunction "16_16") (pintype "passive"))
      (node (ref "R10") (pin "1") (pinfunction "1_1") (pintype "passive"))
      (node (ref "U1") (pin "22") (pinfunction "PB11_22") (pintype "bidirectional"))
      (node (ref "U2") (pin "24") (pinfunction "SDA_24") (pintype "bidirectional"))
    )
    (net (code "50") (name "PB12") (class "Default")
      (node (ref "U1") (pin "25") (pinfunction "PB12_25") (pintype "bidirectional"))
    )
    (net (code "51") (name "PB13") (class "Default")
      (node (ref "U1") (pin "26") (pinfunction "PB13_26") (pintype "bidirectional"))
    )
    (net (code "52") (name "PB14") (class "Default")
      (node (ref "U1") (pin "27") (pinfunction "PB14_27") (pintype "bidirectional"))
    )
    (net (code "53") (name "PB15") (class "Default")
      (node (ref "J4") (pin "17") (pinfunction "17_17") (pintype "passive"))
      (node (ref "U1") (pin "28") (pinfunction "PB15_28") (pintype "bidirectional"))
    )
    (net (code "54") (name "PC13") (class "Default")
      (node (ref "J3") (pin "2") (pinfunction "2_2") (pintype "passive"))
      (node (ref "R1") (pin "1") (pinfunction "1_1") (pintype "passive"))
      (node (ref "U1") (pin "2") (pinfunction "PC13-TAMPER-RTC_2") (pintype "bidirectional"))
    )
    (net (code "55") (name "PC14") (class "Default")
      (node (ref "J3") (pin "3") (pinfunction "3_3") (pintype "passive"))
    )
    (net (code "56") (name "PC15") (class "Default")
      (node (ref "J3") (pin "4") (pinfunction "4_4") (pintype "passive"))
    )
    (net (code "57") (name "RESET") (class "Default")
      (node (ref "C22") (pin "1") (pinfunction "1_1") (pintype "passive"))
      (node (ref "J3") (pin "17") (pinfunction "17_17") (pintype "passive"))
      (node (ref "R5") (pin "1") (pinfunction "1_1") (pintype "passive"))
      (node (ref "S1") (pin "1") (pinfunction "1_1") (pintype "passive"))
      (node (ref "U1") (pin "7") (pinfunction "NRST_7") (pintype "input"))
    )
    (net (code "58") (name "SWCLK") (class "Default")
      (node (ref "J2") (pin "2") (pinfunction "2_2") (pintype "passive"))
      (node (ref "U1") (pin "37") (pinfunction "PA14_37") (pintype "bidirectional"))
    )
    (net (code "59") (name "SWDIO") (class "Default")
      (node (ref "J2") (pin "3") (pinfunction "3_3") (pintype "passive"))
      (node (ref "U1") (pin "34") (pinfunction "PA13_34") (pintype "bidirectional"))
    )
    (net (code "60") (name "VBAT") (class "Default")
      (node (ref "J3") (pin "1") (pinfunction "1_1") (pintype "passive"))
      (node (ref "U1") (pin "1") (pinfunction "VBAT_1") (pintype "bidirectional"))
    )
    (net (code "61") (name "VDD") (class "Default")
      (node (ref "C14") (pin "1") (pinfunction "1_1") (pintype "passive"))
      (node (ref "C15") (pin "2") (pinfunction "2_2") (pintype "passive"))
      (node (ref "C18") (pin "1") (pinfunction "1_1") (pintype "passive"))
      (node (ref "C19") (pin "1") (pinfunction "1_1") (pintype "passive"))
      (node (ref "C20") (pin "1") (pinfunction "1_1") (pintype "passive"))
      (node (ref "C21") (pin "1") (pinfunction "1_1") (pintype "passive"))
      (node (ref "C27") (pin "1") (pinfunction "1_1") (pintype "passive"))
      (node (ref "C28") (pin "1") (pinfunction "1_1") (pintype "passive"))
      (node (ref "C29") (pin "1") (pinfunction "1_1") (pintype "passive"))
      (node (ref "C4") (pin "1") (pinfunction "1_1") (pintype "passive"))
      (node (ref "C5") (pin "1") (pinfunction "1_1") (pintype "passive"))
      (node (ref "J1") (pin "4") (pinfunction "4_4") (pintype "passive"))
      (node (ref "J2") (pin "4") (pinfunction "4_4") (pintype "passive"))
      (node (ref "J3") (pin "18") (pinfunction "18_18") (pintype "passive"))
      (node (ref "J4") (pin "1") (pinfunction "1_1") (pintype "passive"))
      (node (ref "R10") (pin "2") (pinfunction "2_2") (pintype "passive"))
      (node (ref "R5") (pin "2") (pinfunction "2_2") (pintype "passive"))
      (node (ref "R6") (pin "1") (pinfunction "1_1") (pintype "passive"))
      (node (ref "R7") (pin "2") (pinfunction "2_2") (pintype "passive"))
      (node (ref "R8") (pin "2") (pinfunction "2_2") (pintype "passive"))
      (node (ref "R9") (pin "2") (pinfunction "2_2") (pintype "passive"))
      (node (ref "U1") (pin "24") (pinfunction "VDD_24") (pintype "power_in"))
      (node (ref "U1") (pin "36") (pinfunction "VDD_36") (pintype "power_in"))
      (node (ref "U1") (pin "48") (pinfunction "VDD_48") (pintype "power_in"))
      (node (ref "U1") (pin "9") (pinfunction "VDDA_9") (pintype "power_in"))
      (node (ref "U2") (pin "13") (pinfunction "VDD_13") (pintype "power_in"))
      (node (ref "U2") (pin "8") (pinfunction "VLOGIC_8") (pintype "power_in"))
      (node (ref "U4") (pin "15") (pinfunction "VDD_15") (pintype "power_in"))
      (node (ref "U4") (pin "18") (pinfunction "VDD_18") (pintype "power_in"))
      (node (ref "U4") (pin "7") (pinfunction "VDD_7") (pintype "power_in"))
      (node (ref "U5") (pin "5") (pinfunction "OUT_5") (pintype "passive"))
      (node (ref "U6") (pin "1") (pinfunction "VDDIO_1") (pintype "power_in"))
      (node (ref "U6") (pin "10") (pinfunction "VDD_10") (pintype "power_in"))
      (node (ref "U6") (pin "6") (pinfunction "CSB_6") (pintype "input"))
    )
    (net (code "62") (name "VDD_PA") (class "Default")
      (node (ref "C11") (pin "2") (pinfunction "2_2") (pintype "passive"))
      (node (ref "C12") (pin "2") (pinfunction "2_2") (pintype "passive"))
      (node (ref "L1") (pin "2") (pinfunction "2_2") (pintype "passive"))
      (node (ref "U4") (pin "11") (pinfunction "VDD_PA_11") (pintype "power_in"))
    )
    (net (code "63") (name "unconnected-(J5-PadD+)") (class "Default")
      (node (ref "J5") (pin "D+") (pinfunction "D+_D+") (pintype "bidirectional"))
    )
    (net (code "64") (name "unconnected-(J5-PadD-)") (class "Default")
      (node (ref "J5") (pin "D-") (pinfunction "D-_D-") (pintype "bidirectional"))
    )
    (net (code "65") (name "unconnected-(U2-AUX_CL-Pad7)") (class "Default")
      (node (ref "U2") (pin "7") (pinfunction "AUX_CL_7") (pintype "bidirectional"))
    )
    (net (code "66") (name "unconnected-(U2-AUX_DA-Pad6)") (class "Default")
      (node (ref "U2") (pin "6") (pinfunction "AUX_DA_6") (pintype "bidirectional"))
    )
    (net (code "67") (name "unconnected-(U2-NC_2-Pad2)") (class "Default")
      (node (ref "U2") (pin "2") (pinfunction "NC_2_2") (pintype "passive"))
    )
    (net (code "68") (name "unconnected-(U2-NC_3-Pad3)") (class "Default")
      (node (ref "U2") (pin "3") (pinfunction "NC_3_3") (pintype "passive"))
    )
    (net (code "69") (name "unconnected-(U2-NC_4-Pad4)") (class "Default")
      (node (ref "U2") (pin "4") (pinfunction "NC_4_4") (pintype "passive"))
    )
    (net (code "70") (name "unconnected-(U2-NC_5-Pad5)") (class "Default")
      (node (ref "U2") (pin "5") (pinfunction "NC_5_5") (pintype "passive"))
    )
    (net (code "71") (name "unconnected-(U2-NC_14-Pad14)") (class "Default")
      (node (ref "U2") (pin "14") (pinfunction "NC_14_14") (pintype "passive"))
    )
    (net (code "72") (name "unconnected-(U2-NC_15-Pad15)") (class "Default")
      (node (ref "U2") (pin "15") (pinfunction "NC_15_15") (pintype "passive"))
    )
    (net (code "73") (name "unconnected-(U2-NC_16-Pad16)") (class "Default")
      (node (ref "U2") (pin "16") (pinfunction "NC_16_16") (pintype "passive"))
    )
    (net (code "74") (name "unconnected-(U2-NC_17-Pad17)") (class "Default")
      (node (ref "U2") (pin "17") (pinfunction "NC_17_17") (pintype "passive"))
    )
    (net (code "75") (name "unconnected-(U2-RESV_19-Pad19)") (class "Default")
      (node (ref "U2") (pin "19") (pinfunction "RESV_19_19") (pintype "passive"))
    )
    (net (code "76") (name "unconnected-(U2-RESV_21-Pad21)") (class "Default")
      (node (ref "U2") (pin "21") (pinfunction "RESV_21_21") (pintype "passive"))
    )
    (net (code "77") (name "unconnected-(U2-RESV_22-Pad22)") (class "Default")
      (node (ref "U2") (pin "22") (pinfunction "RESV_22_22") (pintype "passive"))
    )
  )
)
